# USB_Hub.net
KiCad netlist of a schematic drawn in Altium Designer
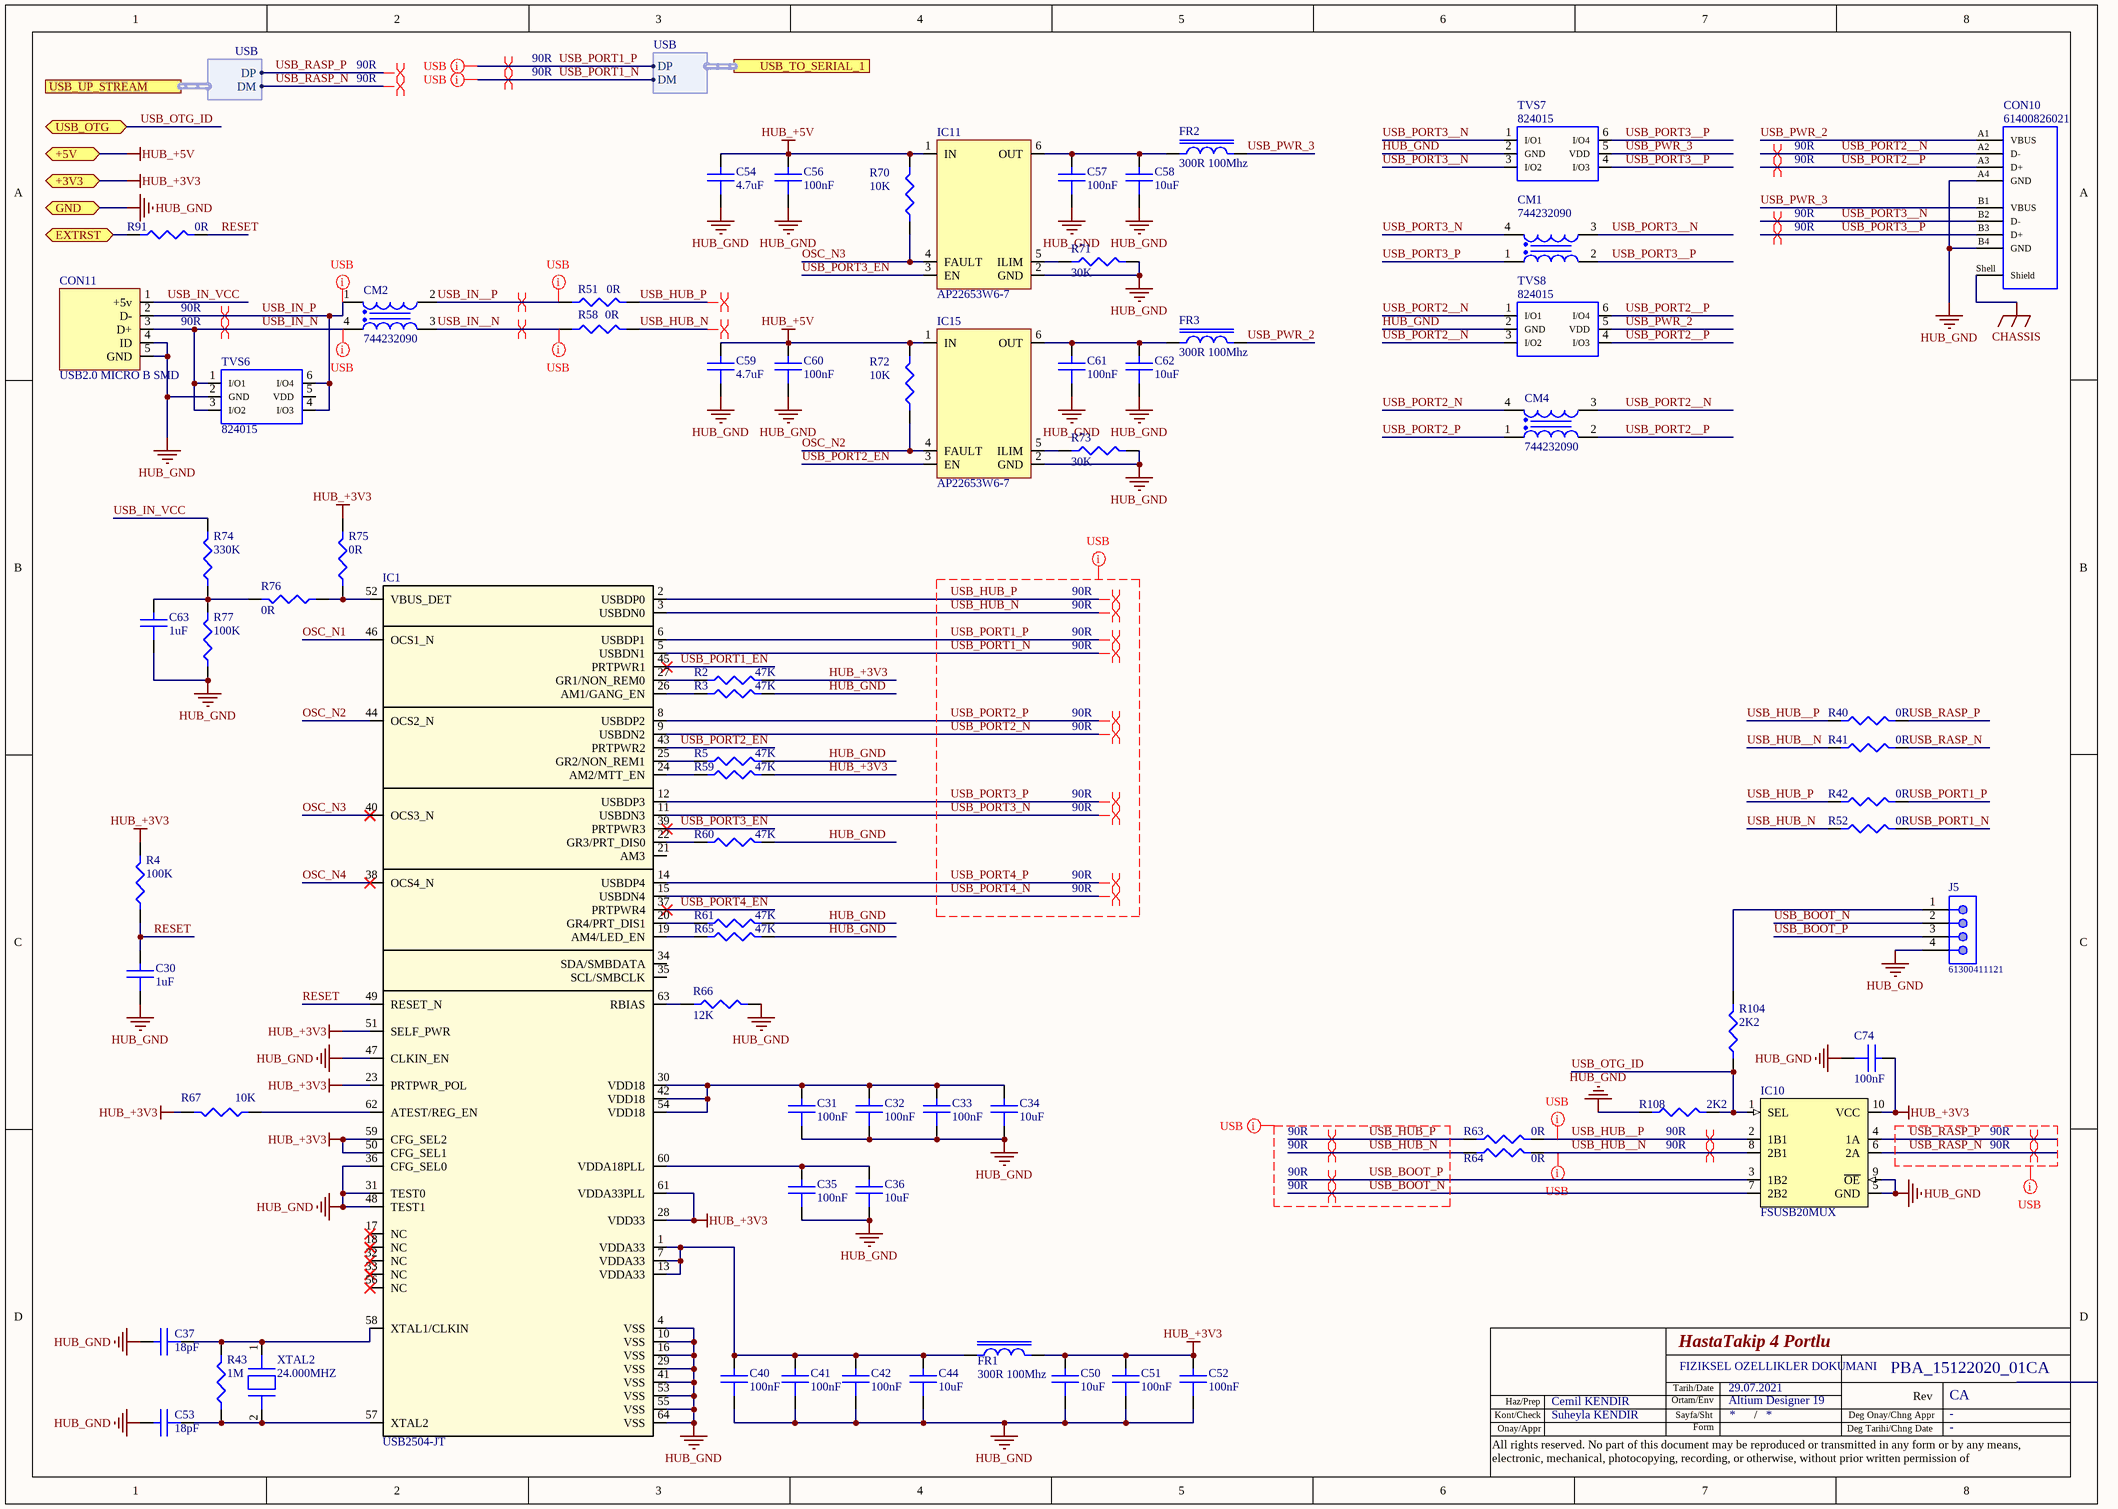
[diagram p0: USB_Hub.SchDoc]

(export (version "E")
  (design (tool "Eeschema 10.0.6"))
  (components
    (comp (ref "C30")
      (value "1uF")
      (footprint "C0603")
      (description "1UF, 16V, X7R, 10%, 0603")
      (fields
        (field (name "MANUFACTURER") "Yageo")
        (field (name "MANUFACTURER PART NUMBER") "CC0603KRX7R7BB105")
      )
      (libsource (lib "McmLibrary") (part "CC0603KRX7R7BB105"))
    )
    (comp (ref "C31")
      (value "100nF")
      (footprint "C0603")
      (description "100nF, 25V, X7R, 10%, 0603")
      (fields
        (field (name "MANUFACTURER") "Yageo")
        (field (name "MANUFACTURER PART NUMBER") "CC0603KRX7R8BB104")
      )
      (libsource (lib "McmLibrary") (part "CC0603KRX7R8BB104"))
    )
    (comp (ref "C32")
      (value "100nF")
      (footprint "C0603")
      (description "100nF, 25V, X7R, 10%, 0603")
      (fields
        (field (name "MANUFACTURER") "Yageo")
        (field (name "MANUFACTURER PART NUMBER") "CC0603KRX7R8BB104")
      )
      (libsource (lib "McmLibrary") (part "CC0603KRX7R8BB104"))
    )
    (comp (ref "C33")
      (value "100nF")
      (footprint "C0603")
      (description "100nF, 25V, X7R, 10%, 0603")
      (fields
        (field (name "MANUFACTURER") "Yageo")
        (field (name "MANUFACTURER PART NUMBER") "CC0603KRX7R8BB104")
      )
      (libsource (lib "McmLibrary") (part "CC0603KRX7R8BB104"))
    )
    (comp (ref "C34")
      (value "10uF")
      (footprint "C0603")
      (description "10uF 10V X5R 20% SMD 0603 85C Paper T/R")
      (fields
        (field (name "MANUFACTURER") "Yageo")
        (field (name "MANUFACTURER PART NUMBER") "CC0603MRX5R6BB106")
      )
      (libsource (lib "McmLibrary") (part "CC0603MRX5R6BB106"))
    )
    (comp (ref "C35")
      (value "100nF")
      (footprint "C0603")
      (description "100nF, 25V, X7R, 10%, 0603")
      (fields
        (field (name "MANUFACTURER") "Yageo")
        (field (name "MANUFACTURER PART NUMBER") "CC0603KRX7R8BB104")
      )
      (libsource (lib "McmLibrary") (part "CC0603KRX7R8BB104"))
    )
    (comp (ref "C36")
      (value "10uF")
      (footprint "C0603")
      (description "10uF 10V X5R 20% SMD 0603 85C Paper T/R")
      (fields
        (field (name "MANUFACTURER") "Yageo")
        (field (name "MANUFACTURER PART NUMBER") "CC0603MRX5R6BB106")
      )
      (libsource (lib "McmLibrary") (part "CC0603MRX5R6BB106"))
    )
    (comp (ref "C37")
      (value "18pF")
      (footprint "C0603")
      (description "18 pF, 50 V, 0603 ± 5%, C0G / NP0")
      (fields
        (field (name "MANUFACTURER") "Yageo")
        (field (name "MANUFACTURER PART NUMBER") "CC0603JRNPO9BN180")
      )
      (libsource (lib "McmLibrary") (part "CC0603JRNPO9BN180"))
    )
    (comp (ref "C40")
      (value "100nF")
      (footprint "C0603")
      (description "100nF, 25V, X7R, 10%, 0603")
      (fields
        (field (name "MANUFACTURER") "Yageo")
        (field (name "MANUFACTURER PART NUMBER") "CC0603KRX7R8BB104")
      )
      (libsource (lib "McmLibrary") (part "CC0603KRX7R8BB104"))
    )
    (comp (ref "C41")
      (value "100nF")
      (footprint "C0603")
      (description "100nF, 25V, X7R, 10%, 0603")
      (fields
        (field (name "MANUFACTURER") "Yageo")
        (field (name "MANUFACTURER PART NUMBER") "CC0603KRX7R8BB104")
      )
      (libsource (lib "McmLibrary") (part "CC0603KRX7R8BB104"))
    )
    (comp (ref "C42")
      (value "100nF")
      (footprint "C0603")
      (description "100nF, 25V, X7R, 10%, 0603")
      (fields
        (field (name "MANUFACTURER") "Yageo")
        (field (name "MANUFACTURER PART NUMBER") "CC0603KRX7R8BB104")
      )
      (libsource (lib "McmLibrary") (part "CC0603KRX7R8BB104"))
    )
    (comp (ref "C44")
      (value "10uF")
      (footprint "C0603")
      (description "10uF 10V X5R 20% SMD 0603 85C Paper T/R")
      (fields
        (field (name "MANUFACTURER") "Yageo")
        (field (name "MANUFACTURER PART NUMBER") "CC0603MRX5R6BB106")
      )
      (libsource (lib "McmLibrary") (part "CC0603MRX5R6BB106"))
    )
    (comp (ref "C50")
      (value "10uF")
      (footprint "C0603")
      (description "10uF 10V X5R 20% SMD 0603 85C Paper T/R")
      (fields
        (field (name "MANUFACTURER") "Yageo")
        (field (name "MANUFACTURER PART NUMBER") "CC0603MRX5R6BB106")
      )
      (libsource (lib "McmLibrary") (part "CC0603MRX5R6BB106"))
    )
    (comp (ref "C51")
      (value "100nF")
      (footprint "C0603")
      (description "100nF, 25V, X7R, 10%, 0603")
      (fields
        (field (name "MANUFACTURER") "Yageo")
        (field (name "MANUFACTURER PART NUMBER") "CC0603KRX7R8BB104")
      )
      (libsource (lib "McmLibrary") (part "CC0603KRX7R8BB104"))
    )
    (comp (ref "C52")
      (value "100nF")
      (footprint "C0603")
      (description "100nF, 25V, X7R, 10%, 0603")
      (fields
        (field (name "MANUFACTURER") "Yageo")
        (field (name "MANUFACTURER PART NUMBER") "CC0603KRX7R8BB104")
      )
      (libsource (lib "McmLibrary") (part "CC0603KRX7R8BB104"))
    )
    (comp (ref "C53")
      (value "18pF")
      (footprint "C0603")
      (description "18 pF, 50 V, 0603 ± 5%, C0G / NP0")
      (fields
        (field (name "MANUFACTURER") "Yageo")
        (field (name "MANUFACTURER PART NUMBER") "CC0603JRNPO9BN180")
      )
      (libsource (lib "McmLibrary") (part "CC0603JRNPO9BN180"))
    )
    (comp (ref "C54")
      (value "4.7uF")
      (footprint "C0603")
      (description "4.7uF 6.3V X7R 0603")
      (fields
        (field (name "MANUFACTURER") "Yageo")
        (field (name "MANUFACTURER PART NUMBER") "CC0603MRX7R5BB475")
      )
      (libsource (lib "McmLibrary") (part "CC0603MRX7R5BB475"))
    )
    (comp (ref "C56")
      (value "100nF")
      (footprint "C0603")
      (description "100nF, 25V, X7R, 10%, 0603")
      (fields
        (field (name "MANUFACTURER") "Yageo")
        (field (name "MANUFACTURER PART NUMBER") "CC0603KRX7R8BB104")
      )
      (libsource (lib "McmLibrary") (part "CC0603KRX7R8BB104"))
    )
    (comp (ref "C57")
      (value "100nF")
      (footprint "C0603")
      (description "100nF, 25V, X7R, 10%, 0603")
      (fields
        (field (name "MANUFACTURER") "Yageo")
        (field (name "MANUFACTURER PART NUMBER") "CC0603KRX7R8BB104")
      )
      (libsource (lib "McmLibrary") (part "CC0603KRX7R8BB104"))
    )
    (comp (ref "C58")
      (value "10uF")
      (footprint "C0603")
      (description "10uF 10V X5R 20% SMD 0603 85C Paper T/R")
      (fields
        (field (name "MANUFACTURER") "Yageo")
        (field (name "MANUFACTURER PART NUMBER") "CC0603MRX5R6BB106")
      )
      (libsource (lib "McmLibrary") (part "CC0603MRX5R6BB106"))
    )
    (comp (ref "C59")
      (value "4.7uF")
      (footprint "C0603")
      (description "4.7uF 6.3V X7R 0603")
      (fields
        (field (name "MANUFACTURER") "Yageo")
        (field (name "MANUFACTURER PART NUMBER") "CC0603MRX7R5BB475")
      )
      (libsource (lib "McmLibrary") (part "CC0603MRX7R5BB475"))
    )
    (comp (ref "C60")
      (value "100nF")
      (footprint "C0603")
      (description "100nF, 25V, X7R, 10%, 0603")
      (fields
        (field (name "MANUFACTURER") "Yageo")
        (field (name "MANUFACTURER PART NUMBER") "CC0603KRX7R8BB104")
      )
      (libsource (lib "McmLibrary") (part "CC0603KRX7R8BB104"))
    )
    (comp (ref "C61")
      (value "100nF")
      (footprint "C0603")
      (description "100nF, 25V, X7R, 10%, 0603")
      (fields
        (field (name "MANUFACTURER") "Yageo")
        (field (name "MANUFACTURER PART NUMBER") "CC0603KRX7R8BB104")
      )
      (libsource (lib "McmLibrary") (part "CC0603KRX7R8BB104"))
    )
    (comp (ref "C62")
      (value "10uF")
      (footprint "C0603")
      (description "10uF 10V X5R 20% SMD 0603 85C Paper T/R")
      (fields
        (field (name "MANUFACTURER") "Yageo")
        (field (name "MANUFACTURER PART NUMBER") "CC0603MRX5R6BB106")
      )
      (libsource (lib "McmLibrary") (part "CC0603MRX5R6BB106"))
    )
    (comp (ref "C63")
      (value "1uF")
      (footprint "C0603")
      (description "1UF, 16V, X7R, 10%, 0603")
      (fields
        (field (name "MANUFACTURER") "Yageo")
        (field (name "MANUFACTURER PART NUMBER") "CC0603KRX7R7BB105")
      )
      (libsource (lib "McmLibrary") (part "CC0603KRX7R7BB105"))
    )
    (comp (ref "C74")
      (value "100nF")
      (footprint "C0603")
      (description "100nF, 25V, X7R, 10%, 0603")
      (fields
        (field (name "MANUFACTURER") "Yageo")
        (field (name "MANUFACTURER PART NUMBER") "CC0603KRX7R8BB104")
      )
      (libsource (lib "McmLibrary") (part "CC0603KRX7R8BB104"))
    )
    (comp (ref "CM1")
      (value "744232090")
      (footprint "WE-CNSW_1206")
      (description "Common Mode Chokes Dual 90Ohm 100MHz 370mA SMD T/R")
      (fields (field (name "MANUFACTURER") "Wurth Electronics") (field (name "TOLERANCE") "25%"))
      (libsource (lib "McmLibrary") (part "744232090"))
    )
    (comp (ref "CM2")
      (value "744232090")
      (footprint "WE-CNSW_1206")
      (description "Common Mode Chokes Dual 90Ohm 100MHz 370mA SMD T/R")
      (fields (field (name "MANUFACTURER") "Wurth Electronics") (field (name "TOLERANCE") "25%"))
      (libsource (lib "") (part "744232090_1"))
    )
    (comp (ref "CM4")
      (value "744232090")
      (footprint "WE-CNSW_1206")
      (description "Common Mode Chokes Dual 90Ohm 100MHz 370mA SMD T/R")
      (fields (field (name "MANUFACTURER") "Wurth Electronics") (field (name "TOLERANCE") "25%"))
      (libsource (lib "McmLibrary") (part "744232090"))
    )
    (comp (ref "CON10")
      (value "61400826021")
      (footprint "61400826021")
      (description "CONN RCPT USB2.0 TYPEA STACK R/A")
      (fields (field (name "MANUFACTURER") "Wurth Electronics"))
      (libsource (lib "McmLibrary") (part "61400826021"))
    )
    (comp (ref "CON11")
      (value "USB2.0 MICRO B SMD")
      (footprint "USB CON B FEMALE")
      (description "CONN RCPT USB2.0 MICRO B SMD R/A")
      (fields
        (field (name "MANUFACTURER") "Amphenol FCI")
        (field (name "MANUFACTURER PART NUMBER") "10118192-0001LF")
      )
      (libsource (lib "McmLibrary") (part "10118192-0001LF"))
    )
    (comp (ref "FR1")
      (value "300R 100Mhz")
      (footprint "WE-CBF_0603_High Current")
      (description "FERRITE BEAD 300 OHM 0603 1LN")
      (fields
        (field (name "MANUFACTURER") "Wurth Electronics")
        (field (name "MANUFACTURER PART NUMBER") "742792641")
      )
      (libsource (lib "McmLibrary") (part "742792641"))
    )
    (comp (ref "FR2")
      (value "300R 100Mhz")
      (footprint "WE-CBF_0603_High Current")
      (description "FERRITE BEAD 300 OHM 0603 1LN")
      (fields
        (field (name "MANUFACTURER") "Wurth Electronics")
        (field (name "MANUFACTURER PART NUMBER") "742792641")
      )
      (libsource (lib "McmLibrary") (part "742792641"))
    )
    (comp (ref "FR3")
      (value "300R 100Mhz")
      (footprint "WE-CBF_0603_High Current")
      (description "FERRITE BEAD 300 OHM 0603 1LN")
      (fields
        (field (name "MANUFACTURER") "Wurth Electronics")
        (field (name "MANUFACTURER PART NUMBER") "742792641")
      )
      (libsource (lib "McmLibrary") (part "742792641"))
    )
    (comp (ref "IC1")
      (value "USB2504-JT")
      (footprint "TQFP64")
      (description "Low Speed/Full Speed/High Speed Compatible 4 Port Hub USB 2.0 1.8V/3.3V 64-Pin TQFP")
      (fields (field (name "MANUFACTURER") "Microchip"))
      (libsource (lib "McmLibrary") (part "USB2504-JT"))
    )
    (comp (ref "IC10")
      (value "FSUSB20MUX")
      (footprint "MSOP-10N")
      (fields (field (name "MANUFACTURER") "ON Semiconductor / Fairchild"))
      (libsource (lib "McmLibrary") (part "FSUSB20MUX"))
    )
    (comp (ref "IC11")
      (value "AP22653W6-7")
      (footprint "SOT23-6")
      (description "Power Switch/Driver 1:1 P-Channel 2.1A SOT-23-6")
      (fields (field (name "MANUFACTURER") "Diodes"))
      (libsource (lib "LoadDrivers") (part "AP22653W6-7"))
    )
    (comp (ref "IC15")
      (value "AP22653W6-7")
      (footprint "SOT23-6")
      (description "Power Switch/Driver 1:1 P-Channel 2.1A SOT-23-6")
      (fields (field (name "MANUFACTURER") "Diodes"))
      (libsource (lib "LoadDrivers") (part "AP22653W6-7"))
    )
    (comp (ref "J5")
      (value "61300411121")
      (footprint "61300411121")
      (description "WR-PHD Pin Header, THT, pitch 2.54mm, Single Row, Vertical, 4pin")
      (fields (field (name "MANUFACTURER") "Wurth Electronics") (field (name "PUBLISHER") "Wurth Elektronik"))
      (libsource (lib "McmLibrary") (part "61300411121"))
    )
    (comp (ref "R2")
      (value "47K")
      (footprint "R0603")
      (description "47K, 50V, 1/10W, 1%, 0603")
      (fields
        (field (name "MANUFACTURER") "Yageo")
        (field (name "MANUFACTURER PART NUMBER") "RC0603FR-0747KL")
      )
      (libsource (lib "McmLibrary") (part "RC0603FR-0747KL"))
    )
    (comp (ref "R3")
      (value "47K")
      (footprint "R0603")
      (description "47K, 50V, 1/10W, 1%, 0603")
      (fields
        (field (name "MANUFACTURER") "Yageo")
        (field (name "MANUFACTURER PART NUMBER") "RC0603FR-0747KL")
      )
      (libsource (lib "McmLibrary") (part "RC0603FR-0747KL"))
    )
    (comp (ref "R4")
      (value "100K")
      (footprint "R0603")
      (description "100K Ohm 1% 1/10W 0603")
      (fields
        (field (name "MANUFACTURER") "Yageo")
        (field (name "MANUFACTURER PART NUMBER") "RC0603FR-07100KL")
      )
      (libsource (lib "McmLibrary") (part "RC0603FR-07100KL"))
    )
    (comp (ref "R5")
      (value "47K")
      (footprint "R0603")
      (description "47K, 50V, 1/10W, 1%, 0603")
      (fields
        (field (name "MANUFACTURER") "Yageo")
        (field (name "MANUFACTURER PART NUMBER") "RC0603FR-0747KL")
      )
      (libsource (lib "McmLibrary") (part "RC0603FR-0747KL"))
    )
    (comp (ref "R40")
      (value "0R")
      (footprint "R0402")
      (description "0R, %1, 1/10w,  0402")
      (fields
        (field (name "MANUFACTURER") "Yageo")
        (field (name "MANUFACTURER PART NUMBER") "RC0402FR-070RL")
      )
      (libsource (lib "McmLibrary") (part "RC0402FR-070RL"))
    )
    (comp (ref "R41")
      (value "0R")
      (footprint "R0402")
      (description "0R, %1, 1/10w,  0402")
      (fields
        (field (name "MANUFACTURER") "Yageo")
        (field (name "MANUFACTURER PART NUMBER") "RC0402FR-070RL")
      )
      (libsource (lib "McmLibrary") (part "RC0402FR-070RL"))
    )
    (comp (ref "R42")
      (value "0R")
      (footprint "R0402")
      (description "0R, %1, 1/10w,  0402")
      (fields
        (field (name "MANUFACTURER") "Yageo")
        (field (name "MANUFACTURER PART NUMBER") "RC0402FR-070RL")
      )
      (libsource (lib "McmLibrary") (part "RC0402FR-070RL"))
    )
    (comp (ref "R43")
      (value "1M")
      (footprint "R0603")
      (description "1M 1% 1/10W 0603")
      (fields
        (field (name "MANUFACTURER") "Yageo")
        (field (name "MANUFACTURER PART NUMBER") "RC0603FR-071ML")
      )
      (libsource (lib "McmLibrary") (part "RC0603FR-071ML"))
    )
    (comp (ref "R51")
      (value "0R")
      (footprint "R0402")
      (description "0R, %1, 1/10w,  0402")
      (fields
        (field (name "MANUFACTURER") "Yageo")
        (field (name "MANUFACTURER PART NUMBER") "RC0402FR-070RL")
      )
      (libsource (lib "McmLibrary") (part "RC0402FR-070RL"))
    )
    (comp (ref "R52")
      (value "0R")
      (footprint "R0402")
      (description "0R, %1, 1/10w,  0402")
      (fields
        (field (name "MANUFACTURER") "Yageo")
        (field (name "MANUFACTURER PART NUMBER") "RC0402FR-070RL")
      )
      (libsource (lib "McmLibrary") (part "RC0402FR-070RL"))
    )
    (comp (ref "R58")
      (value "0R")
      (footprint "R0402")
      (description "0R, %1, 1/10w,  0402")
      (fields
        (field (name "MANUFACTURER") "Yageo")
        (field (name "MANUFACTURER PART NUMBER") "RC0402FR-070RL")
      )
      (libsource (lib "McmLibrary") (part "RC0402FR-070RL"))
    )
    (comp (ref "R59")
      (value "47K")
      (footprint "R0603")
      (description "47K, 50V, 1/10W, 1%, 0603")
      (fields
        (field (name "MANUFACTURER") "Yageo")
        (field (name "MANUFACTURER PART NUMBER") "RC0603FR-0747KL")
      )
      (libsource (lib "McmLibrary") (part "RC0603FR-0747KL"))
    )
    (comp (ref "R60")
      (value "47K")
      (footprint "R0603")
      (description "47K, 50V, 1/10W, 1%, 0603")
      (fields
        (field (name "MANUFACTURER") "Yageo")
        (field (name "MANUFACTURER PART NUMBER") "RC0603FR-0747KL")
      )
      (libsource (lib "McmLibrary") (part "RC0603FR-0747KL"))
    )
    (comp (ref "R61")
      (value "47K")
      (footprint "R0603")
      (description "47K, 50V, 1/10W, 1%, 0603")
      (fields
        (field (name "MANUFACTURER") "Yageo")
        (field (name "MANUFACTURER PART NUMBER") "RC0603FR-0747KL")
      )
      (libsource (lib "McmLibrary") (part "RC0603FR-0747KL"))
    )
    (comp (ref "R63")
      (value "0R")
      (footprint "R0402")
      (description "0R, %1, 1/10w,  0402")
      (fields
        (field (name "MANUFACTURER") "Yageo")
        (field (name "MANUFACTURER PART NUMBER") "RC0402FR-070RL")
      )
      (libsource (lib "McmLibrary") (part "RC0402FR-070RL"))
    )
    (comp (ref "R64")
      (value "0R")
      (footprint "R0402")
      (description "0R, %1, 1/10w,  0402")
      (fields
        (field (name "MANUFACTURER") "Yageo")
        (field (name "MANUFACTURER PART NUMBER") "RC0402FR-070RL")
      )
      (libsource (lib "McmLibrary") (part "RC0402FR-070RL"))
    )
    (comp (ref "R65")
      (value "47K")
      (footprint "R0603")
      (description "47K, 50V, 1/10W, 1%, 0603")
      (fields
        (field (name "MANUFACTURER") "Yageo")
        (field (name "MANUFACTURER PART NUMBER") "RC0603FR-0747KL")
      )
      (libsource (lib "McmLibrary") (part "RC0603FR-0747KL"))
    )
    (comp (ref "R66")
      (value "12K")
      (footprint "R0603")
      (description "12 kohm, 0603, 75 V, 1/10 W")
      (fields
        (field (name "MANUFACTURER") "Yageo")
        (field (name "MANUFACTURER PART NUMBER") "RC0603FR-0712KL")
      )
      (libsource (lib "McmLibrary") (part "RC0603FR-0712KL"))
    )
    (comp (ref "R67")
      (value "10K")
      (footprint "R0603")
      (description "10K OHM 1% 1/10W 0603")
      (fields
        (field (name "MANUFACTURER") "Yageo")
        (field (name "MANUFACTURER PART NUMBER") "RT0603FRE0710KL")
      )
      (libsource (lib "McmLibrary") (part "RT0603FRE0710KL"))
    )
    (comp (ref "R70")
      (value "10K")
      (footprint "R0603")
      (description "10K OHM 1% 1/10W 0603")
      (fields
        (field (name "MANUFACTURER") "Yageo")
        (field (name "MANUFACTURER PART NUMBER") "RT0603FRE0710KL")
      )
      (libsource (lib "McmLibrary") (part "RT0603FRE0710KL"))
    )
    (comp (ref "R71")
      (value "30K")
      (footprint "R0603")
      (description "30K Ohm 1% 1/10W 0603")
      (fields
        (field (name "MANUFACTURER") "Yageo")
        (field (name "MANUFACTURER PART NUMBER") "RT0603FRE0730KL")
      )
      (libsource (lib "Resistor") (part "RT0603FRE0730KL"))
    )
    (comp (ref "R72")
      (value "10K")
      (footprint "R0603")
      (description "10K OHM 1% 1/10W 0603")
      (fields
        (field (name "MANUFACTURER") "Yageo")
        (field (name "MANUFACTURER PART NUMBER") "RT0603FRE0710KL")
      )
      (libsource (lib "McmLibrary") (part "RT0603FRE0710KL"))
    )
    (comp (ref "R73")
      (value "30K")
      (footprint "R0603")
      (description "30K Ohm 1% 1/10W 0603")
      (fields
        (field (name "MANUFACTURER") "Yageo")
        (field (name "MANUFACTURER PART NUMBER") "RT0603FRE0730KL")
      )
      (libsource (lib "Resistor") (part "RT0603FRE0730KL"))
    )
    (comp (ref "R74")
      (value "330K")
      (footprint "R0603")
      (description "330K, 1%, 1/10W, 0603")
      (fields
        (field (name "MANUFACTURER") "Yageo")
        (field (name "MANUFACTURER PART NUMBER") "RC0603FR-07330KL")
      )
      (libsource (lib "McmLibrary") (part "RC0603FR-07330KL"))
    )
    (comp (ref "R75")
      (value "0R")
      (footprint "R0603")
      (description "0R ,%1 ,1/10 W ,0603")
      (fields
        (field (name "MANUFACTURER") "Yageo")
        (field (name "MANUFACTURER PART NUMBER") "RC0603FR-070RL")
      )
      (libsource (lib "McmLibrary") (part "RC0603FR-070RL"))
    )
    (comp (ref "R76")
      (value "0R")
      (footprint "R0603")
      (description "0R ,%1 ,1/10 W ,0603")
      (fields
        (field (name "MANUFACTURER") "Yageo")
        (field (name "MANUFACTURER PART NUMBER") "RC0603FR-070RL")
      )
      (libsource (lib "McmLibrary") (part "RC0603FR-070RL"))
    )
    (comp (ref "R77")
      (value "100K")
      (footprint "R0603")
      (description "100K Ohm 1% 1/10W 0603")
      (fields
        (field (name "MANUFACTURER") "Yageo")
        (field (name "MANUFACTURER PART NUMBER") "RC0603FR-07100KL")
      )
      (libsource (lib "McmLibrary") (part "RC0603FR-07100KL"))
    )
    (comp (ref "R91")
      (value "0R")
      (footprint "R0603")
      (description "0R, 1%, 0.1W, 0603")
      (fields
        (field (name "MANUFACTURER") "Yageo")
        (field (name "MANUFACTURER PART NUMBER") "RC0603FR-070RL")
      )
      (libsource (lib "McmLibrary") (part "RC0603FR-070RL"))
    )
    (comp (ref "R104")
      (value "2K2")
      (footprint "R0603")
      (description "2K2, 1%, 0.1W, 0603")
      (fields
        (field (name "MANUFACTURER") "Yageo")
        (field (name "MANUFACTURER PART NUMBER") "RC0603FR-072K2L")
      )
      (libsource (lib "McmLibrary") (part "RC0603FR-072K2L"))
    )
    (comp (ref "R108")
      (value "2K2")
      (footprint "R0603")
      (description "2K2, 1%, 0.1W, 0603")
      (fields
        (field (name "MANUFACTURER") "Yageo")
        (field (name "MANUFACTURER PART NUMBER") "RC0603FR-072K2L")
      )
      (libsource (lib "McmLibrary") (part "RC0603FR-072K2L"))
    )
    (comp (ref "TVS6")
      (value "824015")
      (footprint "SOT-23-6")
      (description "WURTH ELEKTRONIK - 824015 - TVS Diode, 82401 Series, Bidirectional, 5 V, 13 V, SOT-23, 6 Pins")
      (fields (field (name "MANUFACTURER") "Wurth Electronics"))
      (libsource (lib "TVS") (part "824015"))
    )
    (comp (ref "TVS7")
      (value "824015")
      (footprint "SOT-23-6")
      (description "WURTH ELEKTRONIK - 824015 - TVS Diode, 82401 Series, Bidirectional, 5 V, 13 V, SOT-23, 6 Pins")
      (fields (field (name "MANUFACTURER") "Wurth Electronics"))
      (libsource (lib "TVS") (part "824015"))
    )
    (comp (ref "TVS8")
      (value "824015")
      (footprint "SOT-23-6")
      (description "WURTH ELEKTRONIK - 824015 - TVS Diode, 82401 Series, Bidirectional, 5 V, 13 V, SOT-23, 6 Pins")
      (fields (field (name "MANUFACTURER") "Wurth Electronics"))
      (libsource (lib "TVS") (part "824015"))
    )
    (comp (ref "XTAL2")
      (value "24.000MHZ")
      (footprint "CrystalSMD")
      (description "CRYSTAL 24.0000MHZ 18PF SMD")
      (fields
        (field (name "MANUFACTURER") "Abracon")
        (field (name "MANUFACTURER PART NUMBER") "ABLS-24.000MHZ-B2-T")
      )
      (libsource (lib "McmLibrary") (part "ABLS-24.000MHZ-B2-T"))
    )
  )
  (nets
    (net (code "2") (name "/EXTRST") (class "Default")
      (node (ref "R91") (pin "1") (pinfunction "1_1") (pintype "passive"))
    )
    (net (code "3") (name "/OSC_N1") (class "Default")
      (node (ref "IC1") (pin "46") (pinfunction "OCS1_N_46") (pintype "passive"))
    )
    (net (code "4") (name "/OSC_N2") (class "Default")
      (node (ref "IC1") (pin "44") (pinfunction "OCS2_N_44") (pintype "passive"))
      (node (ref "IC15") (pin "4") (pinfunction "FAULT_4") (pintype "passive"))
      (node (ref "R72") (pin "1") (pinfunction "1_1") (pintype "passive"))
    )
    (net (code "5") (name "/OSC_N3") (class "Default")
      (node (ref "IC1") (pin "40") (pinfunction "OCS3_N_40") (pintype "passive"))
      (node (ref "IC11") (pin "4") (pinfunction "FAULT_4") (pintype "passive"))
      (node (ref "R70") (pin "1") (pinfunction "1_1") (pintype "passive"))
    )
    (net (code "6") (name "/OSC_N4") (class "Default")
      (node (ref "IC1") (pin "38") (pinfunction "OCS4_N_38") (pintype "passive+no_connect"))
    )
    (net (code "7") (name "/RESET") (class "Default")
      (node (ref "C30") (pin "1") (pintype "passive"))
      (node (ref "IC1") (pin "49") (pinfunction "RESET_N_49") (pintype "passive"))
      (node (ref "R4") (pin "1") (pinfunction "1_1") (pintype "passive"))
      (node (ref "R91") (pin "2") (pinfunction "2_2") (pintype "passive"))
    )
    (net (code "8") (name "/USB_BOOT_N") (class "Default")
      (node (ref "IC10") (pin "7") (pinfunction "2B2_7") (pintype "bidirectional"))
      (node (ref "J5") (pin "2") (pinfunction "2_2") (pintype "passive"))
    )
    (net (code "9") (name "/USB_BOOT_P") (class "Default")
      (node (ref "IC10") (pin "3") (pinfunction "1B2_3") (pintype "bidirectional"))
      (node (ref "J5") (pin "3") (pinfunction "3_3") (pintype "passive"))
    )
    (net (code "10") (name "/USB_HUB_N") (class "Default")
      (node (ref "IC1") (pin "3") (pinfunction "USBDN0_3") (pintype "passive"))
      (node (ref "R52") (pin "1") (pinfunction "1_1") (pintype "passive"))
      (node (ref "R58") (pin "2") (pinfunction "2_2") (pintype "passive"))
      (node (ref "R64") (pin "1") (pinfunction "1_1") (pintype "passive"))
    )
    (net (code "11") (name "/USB_HUB_P") (class "Default")
      (node (ref "IC1") (pin "2") (pinfunction "USBDP0_2") (pintype "passive"))
      (node (ref "R42") (pin "1") (pinfunction "1_1") (pintype "passive"))
      (node (ref "R51") (pin "2") (pinfunction "2_2") (pintype "passive"))
      (node (ref "R63") (pin "1") (pinfunction "1_1") (pintype "passive"))
    )
    (net (code "12") (name "/USB_HUB__N") (class "Default")
      (node (ref "IC10") (pin "8") (pinfunction "2B1_8") (pintype "bidirectional"))
      (node (ref "R41") (pin "1") (pinfunction "1_1") (pintype "passive"))
      (node (ref "R64") (pin "2") (pinfunction "2_2") (pintype "passive"))
    )
    (net (code "13") (name "/USB_HUB__P") (class "Default")
      (node (ref "IC10") (pin "2") (pinfunction "1B1_2") (pintype "bidirectional"))
      (node (ref "R40") (pin "1") (pinfunction "1_1") (pintype "passive"))
      (node (ref "R63") (pin "2") (pinfunction "2_2") (pintype "passive"))
    )
    (net (code "14") (name "/USB_IN_N") (class "Default")
      (node (ref "CM2") (pin "4") (pinfunction "4_4") (pintype "passive"))
      (node (ref "CON11") (pin "3") (pinfunction "D+_3") (pintype "passive"))
      (node (ref "TVS6") (pin "1") (pinfunction "I/O1_1") (pintype "passive"))
      (node (ref "TVS6") (pin "3") (pinfunction "I/O2_3") (pintype "passive"))
    )
    (net (code "15") (name "/USB_IN_P") (class "Default")
      (node (ref "CM2") (pin "1") (pinfunction "1_1") (pintype "passive"))
      (node (ref "CON11") (pin "2") (pinfunction "D-_2") (pintype "passive"))
      (node (ref "TVS6") (pin "4") (pinfunction "I/O3_4") (pintype "passive"))
      (node (ref "TVS6") (pin "6") (pinfunction "I/O4_6") (pintype "passive"))
    )
    (net (code "16") (name "/USB_IN_VCC") (class "Default")
      (node (ref "CON11") (pin "1") (pinfunction "+5v_1") (pintype "passive"))
      (node (ref "R74") (pin "2") (pinfunction "2_2") (pintype "passive"))
    )
    (net (code "17") (name "/USB_IN__N") (class "Default")
      (node (ref "CM2") (pin "3") (pinfunction "3_3") (pintype "passive"))
      (node (ref "R58") (pin "1") (pinfunction "1_1") (pintype "passive"))
    )
    (net (code "18") (name "/USB_IN__P") (class "Default")
      (node (ref "CM2") (pin "2") (pinfunction "2_2") (pintype "passive"))
      (node (ref "R51") (pin "1") (pinfunction "1_1") (pintype "passive"))
    )
    (net (code "19") (name "/USB_OTG_ID") (class "Default")
      (node (ref "IC10") (pin "1") (pinfunction "SEL_1") (pintype "input"))
      (node (ref "R104") (pin "1") (pinfunction "1_1") (pintype "passive"))
      (node (ref "R108") (pin "2") (pinfunction "2_2") (pintype "passive"))
    )
    (net (code "20") (name "/USB_PORT1_EN") (class "Default")
      (node (ref "IC1") (pin "45") (pinfunction "PRTPWR1_45") (pintype "passive+no_connect"))
    )
    (net (code "21") (name "/USB_PORT1_N") (class "Default")
      (node (ref "IC1") (pin "5") (pinfunction "USBDN1_5") (pintype "passive"))
      (node (ref "R52") (pin "2") (pinfunction "2_2") (pintype "passive"))
    )
    (net (code "22") (name "/USB_PORT1_P") (class "Default")
      (node (ref "IC1") (pin "6") (pinfunction "USBDP1_6") (pintype "passive"))
      (node (ref "R42") (pin "2") (pinfunction "2_2") (pintype "passive"))
    )
    (net (code "23") (name "/USB_PORT2_EN") (class "Default")
      (node (ref "IC1") (pin "43") (pinfunction "PRTPWR2_43") (pintype "passive"))
      (node (ref "IC15") (pin "3") (pinfunction "EN_3") (pintype "passive"))
    )
    (net (code "24") (name "/USB_PORT2_N") (class "Default")
      (node (ref "CM4") (pin "4") (pinfunction "4_4") (pintype "passive"))
      (node (ref "IC1") (pin "9") (pinfunction "USBDN2_9") (pintype "passive"))
    )
    (net (code "25") (name "/USB_PORT2_P") (class "Default")
      (node (ref "CM4") (pin "1") (pinfunction "1_1") (pintype "passive"))
      (node (ref "IC1") (pin "8") (pinfunction "USBDP2_8") (pintype "passive"))
    )
    (net (code "26") (name "/USB_PORT2__N") (class "Default")
      (node (ref "CM4") (pin "3") (pinfunction "3_3") (pintype "passive"))
      (node (ref "CON10") (pin "A2") (pinfunction "D-_A2") (pintype "passive"))
      (node (ref "TVS8") (pin "1") (pinfunction "I/O1_1") (pintype "passive"))
      (node (ref "TVS8") (pin "3") (pinfunction "I/O2_3") (pintype "passive"))
    )
    (net (code "27") (name "/USB_PORT2__P") (class "Default")
      (node (ref "CM4") (pin "2") (pinfunction "2_2") (pintype "passive"))
      (node (ref "CON10") (pin "A3") (pinfunction "D+_A3") (pintype "passive"))
      (node (ref "TVS8") (pin "4") (pinfunction "I/O3_4") (pintype "passive"))
      (node (ref "TVS8") (pin "6") (pinfunction "I/O4_6") (pintype "passive"))
    )
    (net (code "28") (name "/USB_PORT3_EN") (class "Default")
      (node (ref "IC1") (pin "39") (pinfunction "PRTPWR3_39") (pintype "passive"))
      (node (ref "IC11") (pin "3") (pinfunction "EN_3") (pintype "passive"))
    )
    (net (code "29") (name "/USB_PORT3_N") (class "Default")
      (node (ref "CM1") (pin "4") (pinfunction "4_4") (pintype "passive"))
      (node (ref "IC1") (pin "11") (pinfunction "USBDN3_11") (pintype "passive"))
    )
    (net (code "30") (name "/USB_PORT3_P") (class "Default")
      (node (ref "CM1") (pin "1") (pinfunction "1_1") (pintype "passive"))
      (node (ref "IC1") (pin "12") (pinfunction "USBDP3_12") (pintype "passive"))
    )
    (net (code "31") (name "/USB_PORT3__N") (class "Default")
      (node (ref "CM1") (pin "3") (pinfunction "3_3") (pintype "passive"))
      (node (ref "CON10") (pin "B2") (pinfunction "D-_B2") (pintype "passive"))
      (node (ref "TVS7") (pin "1") (pinfunction "I/O1_1") (pintype "passive"))
      (node (ref "TVS7") (pin "3") (pinfunction "I/O2_3") (pintype "passive"))
    )
    (net (code "32") (name "/USB_PORT3__P") (class "Default")
      (node (ref "CM1") (pin "2") (pinfunction "2_2") (pintype "passive"))
      (node (ref "CON10") (pin "B3") (pinfunction "D+_B3") (pintype "passive"))
      (node (ref "TVS7") (pin "4") (pinfunction "I/O3_4") (pintype "passive"))
      (node (ref "TVS7") (pin "6") (pinfunction "I/O4_6") (pintype "passive"))
    )
    (net (code "33") (name "/USB_PORT4_EN") (class "Default")
      (node (ref "IC1") (pin "37") (pinfunction "PRTPWR4_37") (pintype "passive+no_connect"))
    )
    (net (code "34") (name "/USB_PORT4_N") (class "Default")
      (node (ref "IC1") (pin "15") (pinfunction "USBDN4_15") (pintype "passive"))
    )
    (net (code "35") (name "/USB_PORT4_P") (class "Default")
      (node (ref "IC1") (pin "14") (pinfunction "USBDP4_14") (pintype "passive"))
    )
    (net (code "36") (name "/USB_PWR_2") (class "Default")
      (node (ref "CON10") (pin "A1") (pinfunction "VBUS_A1") (pintype "passive"))
      (node (ref "FR3") (pin "2") (pinfunction "2_2") (pintype "passive"))
      (node (ref "TVS8") (pin "5") (pinfunction "VDD_5") (pintype "passive"))
    )
    (net (code "37") (name "/USB_PWR_3") (class "Default")
      (node (ref "CON10") (pin "B1") (pinfunction "VBUS_B1") (pintype "passive"))
      (node (ref "FR2") (pin "2") (pinfunction "2_2") (pintype "passive"))
      (node (ref "TVS7") (pin "5") (pinfunction "VDD_5") (pintype "passive"))
    )
    (net (code "38") (name "/USB_RASP_N") (class "Default")
      (node (ref "IC10") (pin "6") (pinfunction "2A_6") (pintype "bidirectional"))
      (node (ref "R41") (pin "2") (pinfunction "2_2") (pintype "passive"))
    )
    (net (code "39") (name "/USB_RASP_P") (class "Default")
      (node (ref "IC10") (pin "4") (pinfunction "1A_4") (pintype "bidirectional"))
      (node (ref "R40") (pin "2") (pinfunction "2_2") (pintype "passive"))
    )
    (net (code "41") (name "CHASSIS") (class "Default")
      (node (ref "CON10") (pin "Shell") (pinfunction "Shield_Shell") (pintype "passive"))
    )
    (net (code "42") (name "HUB_+3V3") (class "Default")
      (node (ref "C50") (pin "1") (pintype "passive"))
      (node (ref "C51") (pin "1") (pintype "passive"))
      (node (ref "C52") (pin "1") (pintype "passive"))
      (node (ref "C74") (pin "1") (pintype "passive"))
      (node (ref "FR1") (pin "2") (pinfunction "2_2") (pintype "passive"))
      (node (ref "IC1") (pin "23") (pinfunction "PRTPWR_POL_23") (pintype "passive"))
      (node (ref "IC1") (pin "28") (pinfunction "VDD33_28") (pintype "passive"))
      (node (ref "IC1") (pin "50") (pinfunction "CFG_SEL1_50") (pintype "passive"))
      (node (ref "IC1") (pin "51") (pinfunction "SELF_PWR_51") (pintype "passive"))
      (node (ref "IC1") (pin "59") (pinfunction "CFG_SEL2_59") (pintype "passive"))
      (node (ref "IC1") (pin "61") (pinfunction "VDDA33PLL_61") (pintype "passive"))
      (node (ref "IC10") (pin "10") (pinfunction "VCC_10") (pintype "power_in"))
      (node (ref "R2") (pin "2") (pinfunction "2_2") (pintype "passive"))
      (node (ref "R4") (pin "2") (pinfunction "2_2") (pintype "passive"))
      (node (ref "R59") (pin "2") (pinfunction "2_2") (pintype "passive"))
      (node (ref "R67") (pin "2") (pinfunction "2_2") (pintype "passive"))
      (node (ref "R75") (pin "2") (pinfunction "2_2") (pintype "passive"))
    )
    (net (code "43") (name "HUB_+5V") (class "Default")
      (node (ref "C54") (pin "1") (pintype "passive"))
      (node (ref "C56") (pin "1") (pintype "passive"))
      (node (ref "C59") (pin "1") (pintype "passive"))
      (node (ref "C60") (pin "1") (pintype "passive"))
      (node (ref "IC11") (pin "1") (pinfunction "IN_1") (pintype "passive"))
      (node (ref "IC15") (pin "1") (pinfunction "IN_1") (pintype "passive"))
      (node (ref "R70") (pin "2") (pinfunction "2_2") (pintype "passive"))
      (node (ref "R72") (pin "2") (pinfunction "2_2") (pintype "passive"))
    )
    (net (code "44") (name "HUB_GND") (class "Default")
      (node (ref "C30") (pin "2") (pintype "passive"))
      (node (ref "C31") (pin "2") (pintype "passive"))
      (node (ref "C32") (pin "2") (pintype "passive"))
      (node (ref "C33") (pin "2") (pintype "passive"))
      (node (ref "C34") (pin "2") (pintype "passive"))
      (node (ref "C35") (pin "2") (pintype "passive"))
      (node (ref "C36") (pin "2") (pintype "passive"))
      (node (ref "C37") (pin "1") (pintype "passive"))
      (node (ref "C40") (pin "2") (pintype "passive"))
      (node (ref "C41") (pin "2") (pintype "passive"))
      (node (ref "C42") (pin "2") (pintype "passive"))
      (node (ref "C44") (pin "2") (pintype "passive"))
      (node (ref "C50") (pin "2") (pintype "passive"))
      (node (ref "C51") (pin "2") (pintype "passive"))
      (node (ref "C52") (pin "2") (pintype "passive"))
      (node (ref "C53") (pin "1") (pintype "passive"))
      (node (ref "C54") (pin "2") (pintype "passive"))
      (node (ref "C56") (pin "2") (pintype "passive"))
      (node (ref "C57") (pin "2") (pintype "passive"))
      (node (ref "C58") (pin "2") (pintype "passive"))
      (node (ref "C59") (pin "2") (pintype "passive"))
      (node (ref "C60") (pin "2") (pintype "passive"))
      (node (ref "C61") (pin "2") (pintype "passive"))
      (node (ref "C62") (pin "2") (pintype "passive"))
      (node (ref "C63") (pin "2") (pintype "passive"))
      (node (ref "C74") (pin "2") (pintype "passive"))
      (node (ref "CON10") (pin "A4") (pinfunction "GND_A4") (pintype "passive"))
      (node (ref "CON10") (pin "B4") (pinfunction "GND_B4") (pintype "passive"))
      (node (ref "CON11") (pin "4") (pinfunction "ID_4") (pintype "passive"))
      (node (ref "CON11") (pin "5") (pinfunction "GND_5") (pintype "passive"))
      (node (ref "IC1") (pin "10") (pinfunction "VSS_10") (pintype "passive"))
      (node (ref "IC1") (pin "16") (pinfunction "VSS_16") (pintype "passive"))
      (node (ref "IC1") (pin "29") (pinfunction "VSS_29") (pintype "passive"))
      (node (ref "IC1") (pin "31") (pinfunction "TEST0_31") (pintype "passive"))
      (node (ref "IC1") (pin "36") (pinfunction "CFG_SEL0_36") (pintype "passive"))
      (node (ref "IC1") (pin "4") (pinfunction "VSS_4") (pintype "passive"))
      (node (ref "IC1") (pin "41") (pinfunction "VSS_41") (pintype "passive"))
      (node (ref "IC1") (pin "47") (pinfunction "CLKIN_EN_47") (pintype "passive"))
      (node (ref "IC1") (pin "48") (pinfunction "TEST1_48") (pintype "passive"))
      (node (ref "IC1") (pin "53") (pinfunction "VSS_53") (pintype "passive"))
      (node (ref "IC1") (pin "55") (pinfunction "VSS_55") (pintype "passive"))
      (node (ref "IC1") (pin "64") (pinfunction "VSS_64") (pintype "passive"))
      (node (ref "IC10") (pin "5") (pinfunction "GND_5") (pintype "power_in"))
      (node (ref "IC10") (pin "9") (pinfunction "~{OE}_9") (pintype "input"))
      (node (ref "IC11") (pin "2") (pinfunction "GND_2") (pintype "passive"))
      (node (ref "IC15") (pin "2") (pinfunction "GND_2") (pintype "passive"))
      (node (ref "J5") (pin "4") (pinfunction "4_4") (pintype "passive"))
      (node (ref "R108") (pin "1") (pinfunction "1_1") (pintype "passive"))
      (node (ref "R3") (pin "2") (pinfunction "2_2") (pintype "passive"))
      (node (ref "R5") (pin "2") (pinfunction "2_2") (pintype "passive"))
      (node (ref "R60") (pin "2") (pinfunction "2_2") (pintype "passive"))
      (node (ref "R61") (pin "2") (pinfunction "2_2") (pintype "passive"))
      (node (ref "R65") (pin "2") (pinfunction "2_2") (pintype "passive"))
      (node (ref "R66") (pin "2") (pinfunction "2_2") (pintype "passive"))
      (node (ref "R71") (pin "2") (pinfunction "2_2") (pintype "passive"))
      (node (ref "R73") (pin "2") (pinfunction "2_2") (pintype "passive"))
      (node (ref "R77") (pin "1") (pinfunction "1_1") (pintype "passive"))
      (node (ref "TVS6") (pin "2") (pinfunction "GND_2") (pintype "passive"))
      (node (ref "TVS7") (pin "2") (pinfunction "GND_2") (pintype "passive"))
      (node (ref "TVS8") (pin "2") (pinfunction "GND_2") (pintype "passive"))
    )
    (net (code "45") (name "Net-(C31-Pad1)") (class "Default")
      (node (ref "C31") (pin "1") (pintype "passive"))
      (node (ref "C32") (pin "1") (pintype "passive"))
      (node (ref "C33") (pin "1") (pintype "passive"))
      (node (ref "C34") (pin "1") (pintype "passive"))
      (node (ref "IC1") (pin "30") (pinfunction "VDD18_30") (pintype "passive"))
      (node (ref "IC1") (pin "42") (pinfunction "VDD18_42") (pintype "passive"))
      (node (ref "IC1") (pin "54") (pinfunction "VDD18_54") (pintype "passive"))
    )
    (net (code "46") (name "Net-(C40-Pad1)") (class "Default")
      (node (ref "C40") (pin "1") (pintype "passive"))
      (node (ref "C41") (pin "1") (pintype "passive"))
      (node (ref "C42") (pin "1") (pintype "passive"))
      (node (ref "C44") (pin "1") (pintype "passive"))
      (node (ref "FR1") (pin "1") (pinfunction "1_1") (pintype "passive"))
      (node (ref "IC1") (pin "1") (pinfunction "VDDA33_1") (pintype "passive"))
      (node (ref "IC1") (pin "13") (pinfunction "VDDA33_13") (pintype "passive"))
      (node (ref "IC1") (pin "7") (pinfunction "VDDA33_7") (pintype "passive"))
    )
    (net (code "47") (name "Net-(C63-Pad1)") (class "Default")
      (node (ref "C63") (pin "1") (pintype "passive"))
      (node (ref "R74") (pin "1") (pinfunction "1_1") (pintype "passive"))
      (node (ref "R76") (pin "2") (pinfunction "2_2") (pintype "passive"))
      (node (ref "R77") (pin "2") (pinfunction "2_2") (pintype "passive"))
    )
    (net (code "48") (name "Net-(IC1-AM1{slash}GANG_EN)") (class "Default")
      (node (ref "IC1") (pin "26") (pinfunction "AM1/GANG_EN_26") (pintype "passive"))
      (node (ref "R3") (pin "1") (pinfunction "1_1") (pintype "passive"))
    )
    (net (code "49") (name "Net-(IC1-AM2{slash}MTT_EN)") (class "Default")
      (node (ref "IC1") (pin "24") (pinfunction "AM2/MTT_EN_24") (pintype "passive"))
      (node (ref "R59") (pin "1") (pinfunction "1_1") (pintype "passive"))
    )
    (net (code "50") (name "Net-(IC1-AM4{slash}LED_EN)") (class "Default")
      (node (ref "IC1") (pin "19") (pinfunction "AM4/LED_EN_19") (pintype "passive"))
      (node (ref "R65") (pin "1") (pinfunction "1_1") (pintype "passive"))
    )
    (net (code "51") (name "Net-(IC1-ATEST{slash}REG_EN)") (class "Default")
      (node (ref "IC1") (pin "62") (pinfunction "ATEST/REG_EN_62") (pintype "passive"))
      (node (ref "R67") (pin "1") (pinfunction "1_1") (pintype "passive"))
    )
    (net (code "52") (name "Net-(IC1-GR1{slash}NON_REM0)") (class "Default")
      (node (ref "IC1") (pin "27") (pinfunction "GR1/NON_REM0_27") (pintype "passive"))
      (node (ref "R2") (pin "1") (pinfunction "1_1") (pintype "passive"))
    )
    (net (code "53") (name "Net-(IC1-GR2{slash}NON_REM1)") (class "Default")
      (node (ref "IC1") (pin "25") (pinfunction "GR2/NON_REM1_25") (pintype "passive"))
      (node (ref "R5") (pin "1") (pinfunction "1_1") (pintype "passive"))
    )
    (net (code "54") (name "Net-(IC1-GR3{slash}PRT_DIS0)") (class "Default")
      (node (ref "IC1") (pin "22") (pinfunction "GR3/PRT_DIS0_22") (pintype "passive"))
      (node (ref "R60") (pin "1") (pinfunction "1_1") (pintype "passive"))
    )
    (net (code "55") (name "Net-(IC1-GR4{slash}PRT_DIS1)") (class "Default")
      (node (ref "IC1") (pin "20") (pinfunction "GR4/PRT_DIS1_20") (pintype "passive"))
      (node (ref "R61") (pin "1") (pinfunction "1_1") (pintype "passive"))
    )
    (net (code "56") (name "Net-(IC1-RBIAS)") (class "Default")
      (node (ref "IC1") (pin "63") (pinfunction "RBIAS_63") (pintype "passive"))
      (node (ref "R66") (pin "1") (pinfunction "1_1") (pintype "passive"))
    )
    (net (code "57") (name "Net-(IC1-VBUS_DET)") (class "Default")
      (node (ref "IC1") (pin "52") (pinfunction "VBUS_DET_52") (pintype "passive"))
      (node (ref "R75") (pin "1") (pinfunction "1_1") (pintype "passive"))
      (node (ref "R76") (pin "1") (pinfunction "1_1") (pintype "passive"))
    )
    (net (code "58") (name "Net-(IC1-VDDA18PLL)") (class "Default")
      (node (ref "C35") (pin "1") (pintype "passive"))
      (node (ref "C36") (pin "1") (pintype "passive"))
      (node (ref "IC1") (pin "60") (pinfunction "VDDA18PLL_60") (pintype "passive"))
    )
    (net (code "59") (name "Net-(IC1-XTAL1{slash}CLKIN)") (class "Default")
      (node (ref "C37") (pin "2") (pintype "passive"))
      (node (ref "IC1") (pin "58") (pinfunction "XTAL1/CLKIN_58") (pintype "passive"))
      (node (ref "R43") (pin "2") (pinfunction "2_2") (pintype "passive"))
      (node (ref "XTAL2") (pin "1") (pinfunction "1_1") (pintype "passive"))
    )
    (net (code "60") (name "Net-(IC1-XTAL2)") (class "Default")
      (node (ref "C53") (pin "2") (pintype "passive"))
      (node (ref "IC1") (pin "57") (pinfunction "XTAL2_57") (pintype "passive"))
      (node (ref "R43") (pin "1") (pinfunction "1_1") (pintype "passive"))
      (node (ref "XTAL2") (pin "2") (pinfunction "2_2") (pintype "passive"))
    )
    (net (code "61") (name "Net-(IC11-ILIM)") (class "Default")
      (node (ref "IC11") (pin "5") (pinfunction "ILIM_5") (pintype "passive"))
      (node (ref "R71") (pin "1") (pinfunction "1_1") (pintype "passive"))
    )
    (net (code "62") (name "Net-(IC11-OUT)") (class "Default")
      (node (ref "C57") (pin "1") (pintype "passive"))
      (node (ref "C58") (pin "1") (pintype "passive"))
      (node (ref "FR2") (pin "1") (pinfunction "1_1") (pintype "passive"))
      (node (ref "IC11") (pin "6") (pinfunction "OUT_6") (pintype "passive"))
    )
    (net (code "63") (name "Net-(IC15-ILIM)") (class "Default")
      (node (ref "IC15") (pin "5") (pinfunction "ILIM_5") (pintype "passive"))
      (node (ref "R73") (pin "1") (pinfunction "1_1") (pintype "passive"))
    )
    (net (code "64") (name "Net-(IC15-OUT)") (class "Default")
      (node (ref "C61") (pin "1") (pintype "passive"))
      (node (ref "C62") (pin "1") (pintype "passive"))
      (node (ref "FR3") (pin "1") (pinfunction "1_1") (pintype "passive"))
      (node (ref "IC15") (pin "6") (pinfunction "OUT_6") (pintype "passive"))
    )
    (net (code "65") (name "Net-(J5-Pad1)") (class "Default")
      (node (ref "J5") (pin "1") (pinfunction "1_1") (pintype "passive"))
      (node (ref "R104") (pin "2") (pinfunction "2_2") (pintype "passive"))
    )
    (net (code "66") (name "unconnected-(IC1-AM3-Pad21)") (class "Default")
      (node (ref "IC1") (pin "21") (pinfunction "AM3_21") (pintype "passive"))
    )
    (net (code "67") (name "unconnected-(IC1-NC-Pad17)") (class "Default")
      (node (ref "IC1") (pin "17") (pinfunction "NC_17") (pintype "passive+no_connect"))
    )
    (net (code "68") (name "unconnected-(IC1-NC-Pad18)") (class "Default")
      (node (ref "IC1") (pin "18") (pinfunction "NC_18") (pintype "passive+no_connect"))
    )
    (net (code "69") (name "unconnected-(IC1-NC-Pad32)") (class "Default")
      (node (ref "IC1") (pin "32") (pinfunction "NC_32") (pintype "passive+no_connect"))
    )
    (net (code "70") (name "unconnected-(IC1-NC-Pad33)") (class "Default")
      (node (ref "IC1") (pin "33") (pinfunction "NC_33") (pintype "passive+no_connect"))
    )
    (net (code "71") (name "unconnected-(IC1-NC-Pad56)") (class "Default")
      (node (ref "IC1") (pin "56") (pinfunction "NC_56") (pintype "passive+no_connect"))
    )
    (net (code "72") (name "unconnected-(IC1-SCL{slash}SMBCLK-Pad35)") (class "Default")
      (node (ref "IC1") (pin "35") (pinfunction "SCL/SMBCLK_35") (pintype "passive"))
    )
    (net (code "73") (name "unconnected-(IC1-SDA{slash}SMBDATA-Pad34)") (class "Default")
      (node (ref "IC1") (pin "34") (pinfunction "SDA/SMBDATA_34") (pintype "passive"))
    )
    (net (code "74") (name "unconnected-(TVS6-VDD-Pad5)") (class "Default")
      (node (ref "TVS6") (pin "5") (pinfunction "VDD_5") (pintype "passive"))
    )
  )
)
